# Capacitive_touch_activated_led.net
KiCad netlist of a schematic drawn in Altium Designer
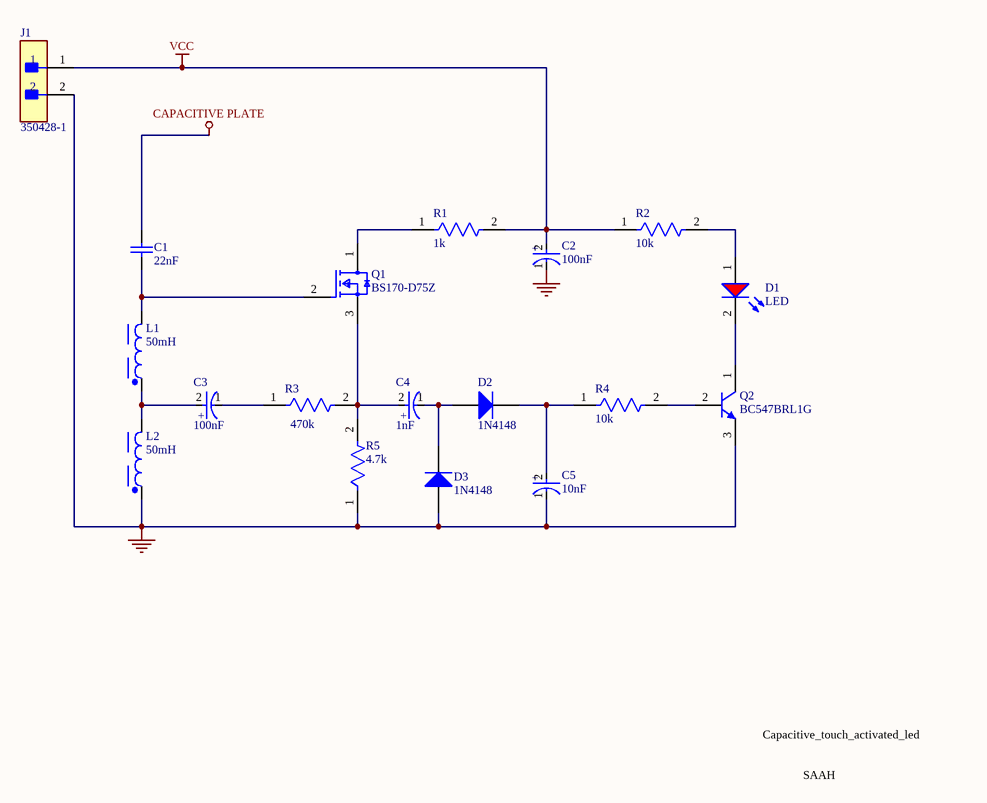
[diagram p0: Capacitive_touch_activated_led.SchDoc]

(export (version "E")
  (design (tool "Eeschema 10.0.6"))
  (components
    (comp (ref "C1")
      (value "22nF")
      (footprint "WCAP-FTXX_L13W4.5H9.5_CS")
      (description "890334023011CS WCAP-FTXX Film Capacitor 22nF 310Vac")
      (fields (field (name "TOLERANCE") "10%"))
      (libsource (lib "Altium Content Vault") (part "Capacitor_Non-Polarized"))
    )
    (comp (ref "C2")
      (value "100nF")
      (footprint "FP-HDF-MFG")
      (description "CAP ALUM 10UF 20% 100V SMD")
      (fields (field (name "VOLTAGE") "100V") (field (name "TOLERANCE") "20%"))
      (libsource (lib "Altium Content Vault") (part "cf48714ba7e38822c1575c7ec0b6d1f"))
    )
    (comp (ref "C3")
      (value "100nF")
      (footprint "FP-HDF-MFG")
      (description "CAP ALUM 10UF 20% 100V SMD")
      (fields (field (name "VOLTAGE") "100V") (field (name "TOLERANCE") "20%"))
      (libsource (lib "Altium Content Vault") (part "cf48714ba7e38822c1575c7ec0b6d1f"))
    )
    (comp (ref "C4")
      (value "1nF")
      (footprint "FP-HDF-MFG")
      (description "CAP ALUM 10UF 20% 100V SMD")
      (fields (field (name "VOLTAGE") "100V") (field (name "TOLERANCE") "20%"))
      (libsource (lib "Altium Content Vault") (part "cf48714ba7e38822c1575c7ec0b6d1f"))
    )
    (comp (ref "C5")
      (value "10nF")
      (footprint "FP-HDF-MFG")
      (description "CAP ALUM 10UF 20% 100V SMD")
      (fields (field (name "VOLTAGE") "100V") (field (name "TOLERANCE") "20%"))
      (libsource (lib "Altium Content Vault") (part "cf48714ba7e38822c1575c7ec0b6d1f"))
    )
    (comp (ref "D1")
      (value "LED")
      (footprint "WL-TMRC_D5.9H8.7")
      (description "151051SS04000 WL-TMRC THT Mono-color Round Color")
      (libsource (lib "Altium Content Vault") (part "LED_Red_1A-2K"))
    )
    (comp (ref "D2")
      (value "1N4148")
      (footprint "NXP-SOD27-2_V")
      (description "High-speed Diode, 100 V, 450 mA, 2-Pin SOD27, RoHS")
      (fields (field (name "MANUFACTURER") "NXP Semiconductors"))
      (libsource (lib "Altium Content Vault") (part "NXP-A1K2-2"))
    )
    (comp (ref "D3")
      (value "1N4148")
      (footprint "NXP-SOD27-2_V")
      (description "High-speed Diode, 100 V, 450 mA, 2-Pin SOD27, RoHS")
      (fields (field (name "MANUFACTURER") "NXP Semiconductors"))
      (libsource (lib "Altium Content Vault") (part "NXP-A1K2-2"))
    )
    (comp (ref "J1")
      (value "350428-1")
      (footprint "FP-350428-1-MFG")
      (description "CONN HEADER VERT 2POS 6.35MM")
      (fields
        (field (name "OCTOPART") "https://octopart.com/350428-1-te+connectivity-46505355")
        (field (name "MANUFACTURER") "TE Connectivity")
      )
      (libsource (lib "Altium Content Vault") (part "3bc925449376181038e59eaffc5286c"))
    )
    (comp (ref "L1")
      (value "50mH")
      (footprint "WE-TI_8012")
      (libsource (lib "Altium Content Vault") (part "Inductor - 2"))
    )
    (comp (ref "L2")
      (value "50mH")
      (footprint "WE-TI_8012")
      (libsource (lib "Altium Content Vault") (part "Inductor - 2"))
    )
    (comp (ref "Q1")
      (value "BS170-D75Z")
      (footprint "FP-135AR-MFG")
      (description "BS170-D75Z BS170 Series 60 V 5 Ohm N-Channel Enhancement Mode Field Effect Transistor-TO-92")
      (libsource (lib "Altium Content Vault") (part "ec6d31c2f3d83daa26b14bce35f384c"))
    )
    (comp (ref "Q2")
      (value "BC547BRL1G")
      (footprint "ONSC-TO-92-3-29-11_AM_BL")
      (description "Amplifier Transistor, NPN Silicon, 3-Pin TO-92, Pb-Free, Tape and Reel")
      (fields (field (name "MANUFACTURER") "On Semiconductor"))
      (libsource (lib "Altium Content Vault") (part "ONSC-NPN-C1B2E3-3"))
    )
    (comp (ref "R1")
      (value "1k")
      (footprint "FP-CF14-MFG")
      (description "RES 7.5K OHM 1/4W 5% AXIAL")
      (fields (field (name "TOLERANCE") "5%"))
      (libsource (lib "Altium Content Vault") (part "1029c3af85768c4190bb7ad29bc67b5"))
    )
    (comp (ref "R2")
      (value "10k")
      (footprint "FP-CF14-MFG")
      (description "RES 7.5K OHM 1/4W 5% AXIAL")
      (fields (field (name "TOLERANCE") "5%"))
      (libsource (lib "Altium Content Vault") (part "1029c3af85768c4190bb7ad29bc67b5"))
    )
    (comp (ref "R3")
      (value "470k")
      (footprint "FP-CF14-MFG")
      (description "RES 7.5K OHM 1/4W 5% AXIAL")
      (fields (field (name "TOLERANCE") "5%"))
      (libsource (lib "Altium Content Vault") (part "1029c3af85768c4190bb7ad29bc67b5"))
    )
    (comp (ref "R4")
      (value "10k")
      (footprint "FP-CF14-MFG")
      (description "RES 7.5K OHM 1/4W 5% AXIAL")
      (fields (field (name "TOLERANCE") "5%"))
      (libsource (lib "Altium Content Vault") (part "1029c3af85768c4190bb7ad29bc67b5"))
    )
    (comp (ref "R5")
      (value "4.7k")
      (footprint "FP-CF14-MFG")
      (description "RES 7.5K OHM 1/4W 5% AXIAL")
      (fields (field (name "TOLERANCE") "5%"))
      (libsource (lib "Altium Content Vault") (part "1029c3af85768c4190bb7ad29bc67b5"))
    )
  )
  (nets
    (net (code "1") (name "CAPACITIVE PLATE") (class "Default")
      (node (ref "C1") (pin "2") (pinfunction "2_2") (pintype "passive"))
    )
    (net (code "2") (name "GND") (class "Default")
      (node (ref "C2") (pin "1") (pinfunction "C_1") (pintype "passive"))
      (node (ref "C5") (pin "1") (pinfunction "C_1") (pintype "passive"))
      (node (ref "D3") (pin "1") (pinfunction "A_1") (pintype "passive"))
      (node (ref "J1") (pin "2") (pinfunction "2_2") (pintype "passive"))
      (node (ref "L2") (pin "1") (pinfunction "1_1") (pintype "passive"))
      (node (ref "Q2") (pin "3") (pinfunction "E_3") (pintype "passive"))
      (node (ref "R5") (pin "1") (pinfunction "1_1") (pintype "passive"))
    )
    (net (code "3") (name "Net-(C3-A)") (class "Default")
      (node (ref "C3") (pin "2") (pinfunction "A_2") (pintype "passive"))
      (node (ref "L1") (pin "1") (pinfunction "1_1") (pintype "passive"))
      (node (ref "L2") (pin "2") (pinfunction "2_2") (pintype "passive"))
    )
    (net (code "4") (name "Net-(C3-C)") (class "Default")
      (node (ref "C3") (pin "1") (pinfunction "C_1") (pintype "passive"))
      (node (ref "R3") (pin "1") (pinfunction "1_1") (pintype "passive"))
    )
    (net (code "5") (name "Net-(C4-A)") (class "Default")
      (node (ref "C4") (pin "2") (pinfunction "A_2") (pintype "passive"))
      (node (ref "Q1") (pin "3") (pinfunction "S_3") (pintype "passive"))
      (node (ref "R3") (pin "2") (pinfunction "2_2") (pintype "passive"))
      (node (ref "R5") (pin "2") (pinfunction "2_2") (pintype "passive"))
    )
    (net (code "6") (name "Net-(C4-C)") (class "Default")
      (node (ref "C4") (pin "1") (pinfunction "C_1") (pintype "passive"))
      (node (ref "D2") (pin "1") (pinfunction "A_1") (pintype "passive"))
      (node (ref "D3") (pin "2") (pinfunction "K_2") (pintype "passive"))
    )
    (net (code "7") (name "Net-(C5-A)") (class "Default")
      (node (ref "C5") (pin "2") (pinfunction "A_2") (pintype "passive"))
      (node (ref "D2") (pin "2") (pinfunction "K_2") (pintype "passive"))
      (node (ref "R4") (pin "1") (pinfunction "1_1") (pintype "passive"))
    )
    (net (code "8") (name "Net-(D1-A)") (class "Default")
      (node (ref "D1") (pin "1") (pinfunction "A_1") (pintype "passive"))
      (node (ref "R2") (pin "2") (pinfunction "2_2") (pintype "passive"))
    )
    (net (code "9") (name "Net-(D1-K)") (class "Default")
      (node (ref "D1") (pin "2") (pinfunction "K_2") (pintype "passive"))
      (node (ref "Q2") (pin "1") (pinfunction "C_1") (pintype "passive"))
    )
    (net (code "10") (name "Net-(Q1-D)") (class "Default")
      (node (ref "Q1") (pin "1") (pinfunction "D_1") (pintype "passive"))
      (node (ref "R1") (pin "1") (pinfunction "1_1") (pintype "passive"))
    )
    (net (code "11") (name "Net-(Q1-G)") (class "Default")
      (node (ref "C1") (pin "1") (pinfunction "1_1") (pintype "passive"))
      (node (ref "L1") (pin "2") (pinfunction "2_2") (pintype "passive"))
      (node (ref "Q1") (pin "2") (pinfunction "G_2") (pintype "passive"))
    )
    (net (code "12") (name "Net-(Q2-B)") (class "Default")
      (node (ref "Q2") (pin "2") (pinfunction "B_2") (pintype "passive"))
      (node (ref "R4") (pin "2") (pinfunction "2_2") (pintype "passive"))
    )
    (net (code "13") (name "VCC") (class "Default")
      (node (ref "C2") (pin "2") (pinfunction "A_2") (pintype "passive"))
      (node (ref "J1") (pin "1") (pinfunction "1_1") (pintype "passive"))
      (node (ref "R1") (pin "2") (pinfunction "2_2") (pintype "passive"))
      (node (ref "R2") (pin "1") (pinfunction "1_1") (pintype "passive"))
    )
  )
)
